# SkeinTwister.net
KiCad netlist of a schematic drawn in EAGLE
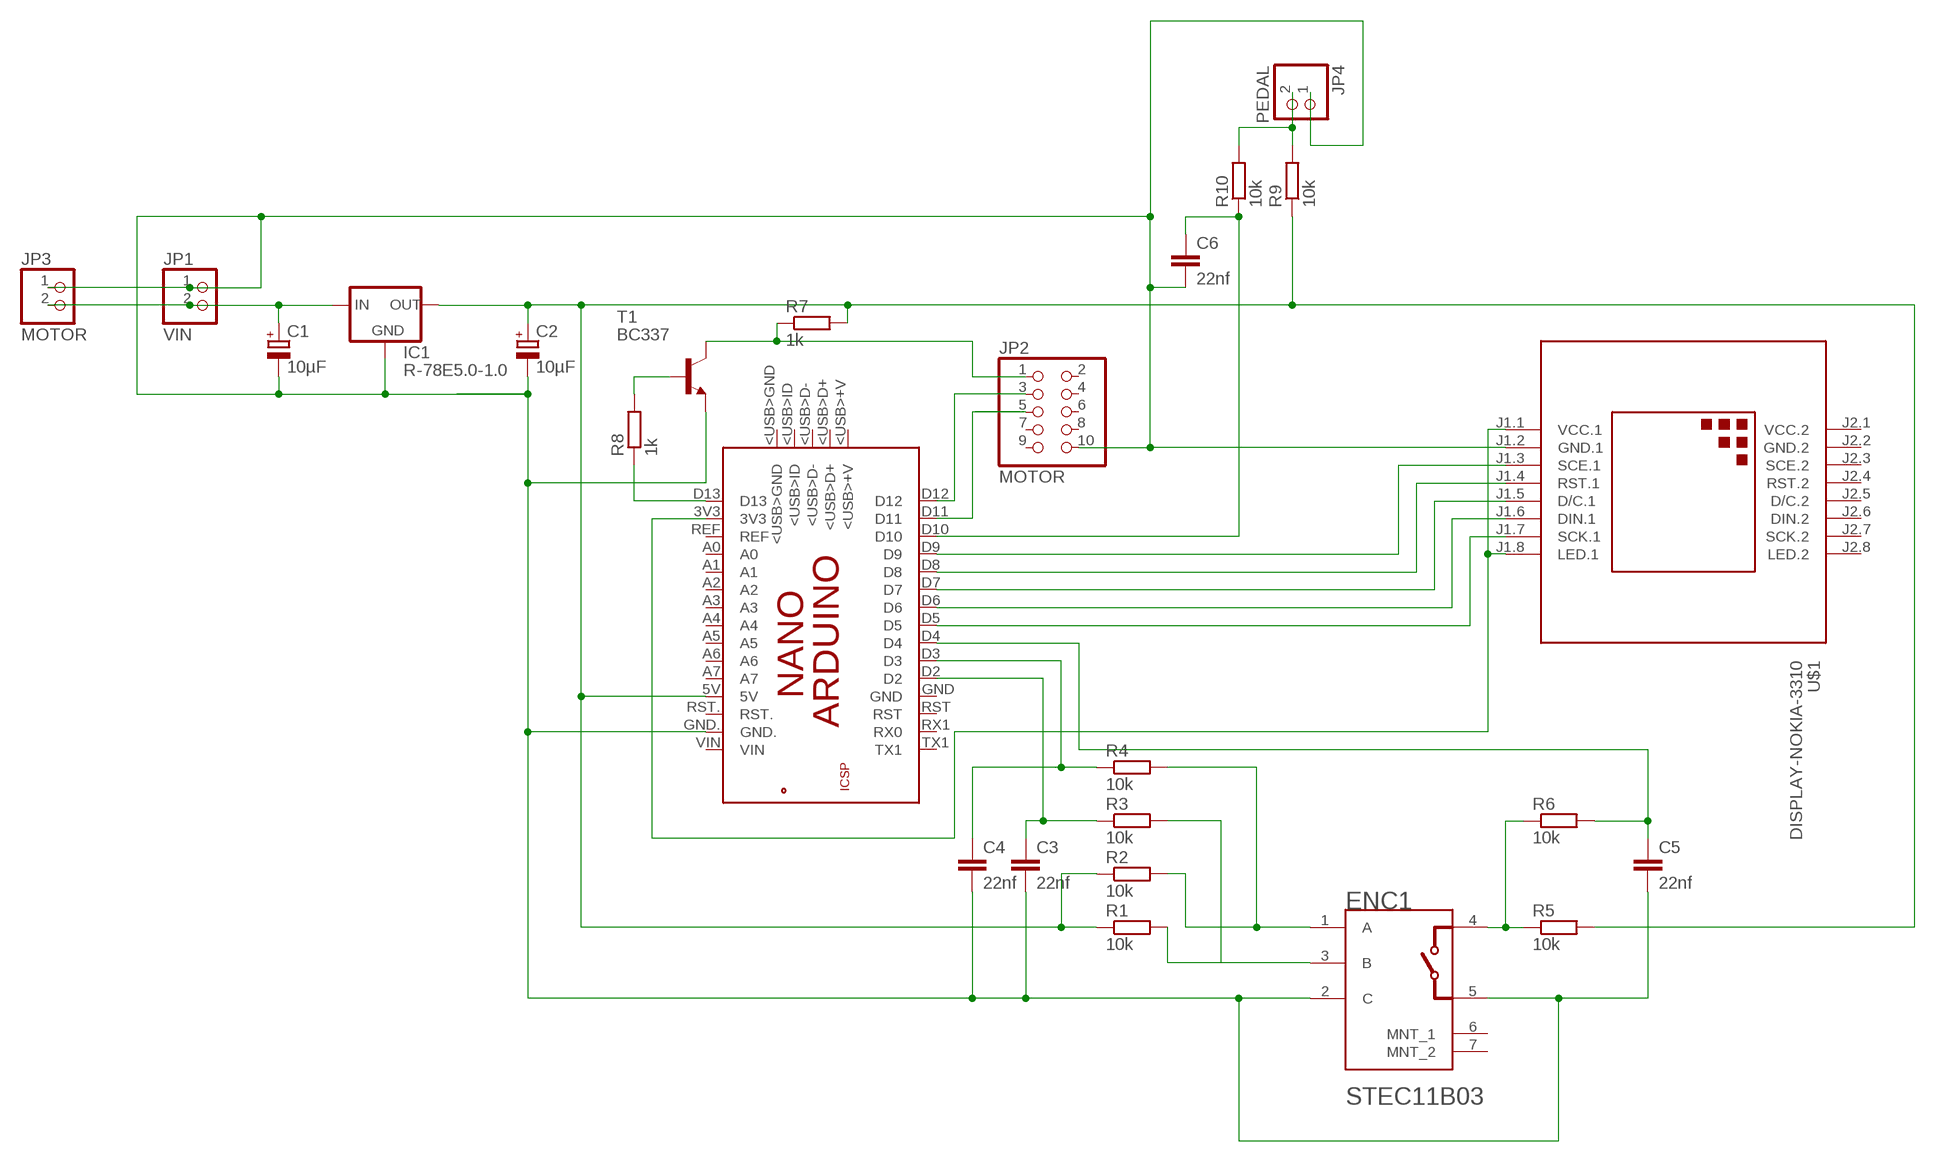
[diagram p0: schematic, sheet 1]

(export (version "E")
  (design (tool "Eeschema 10.0.6"))
  (components
    (comp (ref "C1")
      (value "10µF")
      (footprint "eagle-import:E5-5")
      (libsource (lib "eagle-import") (part "CPOL-EUE5-5"))
    )
    (comp (ref "C2")
      (value "10µF")
      (footprint "eagle-import:E5-5")
      (libsource (lib "eagle-import") (part "CPOL-EUE5-5"))
    )
    (comp (ref "C3")
      (value "22nf")
      (footprint "eagle-import:C025-024X044")
      (libsource (lib "eagle-import") (part "C-EU025-024X044"))
    )
    (comp (ref "C4")
      (value "22nf")
      (footprint "eagle-import:C025-024X044")
      (libsource (lib "eagle-import") (part "C-EU025-024X044"))
    )
    (comp (ref "C5")
      (value "22nf")
      (footprint "eagle-import:C025-024X044")
      (libsource (lib "eagle-import") (part "C-EU025-024X044"))
    )
    (comp (ref "C6")
      (value "22nf")
      (footprint "eagle-import:C025-024X044")
      (libsource (lib "eagle-import") (part "C-EU025-024X044"))
    )
    (comp (ref "ENC1")
      (value "ALPS_STEC11B03ALPS_STEC11B03_0_0")
      (footprint "eagle-import:ALPS_STEC11B03_0")
      (fields (field (name "MF") "ALPS") (field (name "MPN") "STEC11B03"))
      (libsource (lib "eagle-import") (part "ALPS_STEC11B03ALPS_STEC11B03_0_0"))
    )
    (comp (ref "IC1")
      (value "R-78E5.0-1.0")
      (footprint "eagle-import:SIP3")
      (fields (field (name "MF") "Recom") (field (name "MPN") "R-785.0-1.0"))
      (libsource (lib "eagle-import") (part "R-78E-1.05.0"))
    )
    (comp (ref "JP1")
      (value "VIN")
      (footprint "eagle-import:1X02")
      (libsource (lib "eagle-import") (part "PINHD-1X2"))
    )
    (comp (ref "JP2")
      (value "MOTOR")
      (footprint "eagle-import:2X05")
      (libsource (lib "eagle-import") (part "PINHD-2X5"))
    )
    (comp (ref "JP3")
      (value "MOTOR")
      (footprint "eagle-import:1X02")
      (libsource (lib "eagle-import") (part "PINHD-1X2"))
    )
    (comp (ref "JP4")
      (value "PEDAL")
      (footprint "eagle-import:1X02")
      (libsource (lib "eagle-import") (part "PINHD-1X2"))
    )
    (comp (ref "PCB2")
      (value "ARDUINO_NANO")
      (footprint "eagle-import:ARDUINO_NANO")
      (libsource (lib "eagle-import") (part "ARDUINO_NANO"))
    )
    (comp (ref "R1")
      (value "10k")
      (footprint "eagle-import:0204_5")
      (libsource (lib "eagle-import") (part "R-EU_0204/5"))
    )
    (comp (ref "R2")
      (value "10k")
      (footprint "eagle-import:0204_5")
      (libsource (lib "eagle-import") (part "R-EU_0204/5"))
    )
    (comp (ref "R3")
      (value "10k")
      (footprint "eagle-import:0204_5")
      (libsource (lib "eagle-import") (part "R-EU_0204/5"))
    )
    (comp (ref "R4")
      (value "10k")
      (footprint "eagle-import:0204_5")
      (libsource (lib "eagle-import") (part "R-EU_0204/5"))
    )
    (comp (ref "R5")
      (value "10k")
      (footprint "eagle-import:0204_5")
      (libsource (lib "eagle-import") (part "R-EU_0204/5"))
    )
    (comp (ref "R6")
      (value "10k")
      (footprint "eagle-import:0204_5")
      (libsource (lib "eagle-import") (part "R-EU_0204/5"))
    )
    (comp (ref "R7")
      (value "1k")
      (footprint "eagle-import:0204_5")
      (libsource (lib "eagle-import") (part "R-EU_0204/5"))
    )
    (comp (ref "R8")
      (value "1k")
      (footprint "eagle-import:0204_5")
      (libsource (lib "eagle-import") (part "R-EU_0204/5"))
    )
    (comp (ref "R9")
      (value "10k")
      (footprint "eagle-import:0204_5")
      (libsource (lib "eagle-import") (part "R-EU_0204/5"))
    )
    (comp (ref "R10")
      (value "10k")
      (footprint "eagle-import:0204_5")
      (libsource (lib "eagle-import") (part "R-EU_0204/5"))
    )
    (comp (ref "T1")
      (value "BC337")
      (footprint "eagle-import:TO92")
      (libsource (lib "eagle-import") (part "BC337"))
    )
    (comp (ref "U$1")
      (value "DISPLAY-NOKIA-3310")
      (footprint "eagle-import:DISPLAY-NOKIA-3310")
      (libsource (lib "eagle-import") (part "DISPLAY-NOKIA-3310"))
    )
  )
  (nets
    (net (code "1") (name "/GND.2") (class "Default")
      (node (ref "U$1") (pin "J2.2") (pinfunction "GND.2_J2.2") (pintype "power_in"))
    )
    (net (code "2") (name "/VCC.2") (class "Default")
      (node (ref "U$1") (pin "J2.1") (pinfunction "VCC.2_J2.1") (pintype "power_in"))
    )
    (net (code "3") (name "Net-(C3-Pad1)") (class "Default")
      (node (ref "C3") (pin "1") (pinfunction "1_1") (pintype "passive"))
      (node (ref "PCB2") (pin "D2") (pinfunction "D2_D2") (pintype "bidirectional"))
      (node (ref "R3") (pin "1") (pinfunction "1_1") (pintype "passive"))
    )
    (net (code "4") (name "Net-(C4-Pad1)") (class "Default")
      (node (ref "C4") (pin "1") (pinfunction "1_1") (pintype "passive"))
      (node (ref "PCB2") (pin "D3") (pinfunction "D3_D3") (pintype "bidirectional"))
      (node (ref "R4") (pin "1") (pinfunction "1_1") (pintype "passive"))
    )
    (net (code "5") (name "Net-(C5-Pad1)") (class "Default")
      (node (ref "C5") (pin "1") (pinfunction "1_1") (pintype "passive"))
      (node (ref "PCB2") (pin "D4") (pinfunction "D4_D4") (pintype "bidirectional"))
      (node (ref "R6") (pin "2") (pinfunction "2_2") (pintype "passive"))
    )
    (net (code "6") (name "Net-(C6-Pad1)") (class "Default")
      (node (ref "C6") (pin "1") (pinfunction "1_1") (pintype "passive"))
      (node (ref "PCB2") (pin "D10") (pinfunction "D10_D10") (pintype "bidirectional"))
      (node (ref "R10") (pin "1") (pinfunction "1_1") (pintype "passive"))
    )
    (net (code "7") (name "Net-(ENC1-A)") (class "Default")
      (node (ref "ENC1") (pin "1") (pinfunction "A_1") (pintype "passive"))
      (node (ref "R2") (pin "2") (pinfunction "2_2") (pintype "passive"))
      (node (ref "R4") (pin "2") (pinfunction "2_2") (pintype "passive"))
    )
    (net (code "8") (name "Net-(ENC1-B)") (class "Default")
      (node (ref "ENC1") (pin "3") (pinfunction "B_3") (pintype "passive"))
      (node (ref "R1") (pin "2") (pinfunction "2_2") (pintype "passive"))
      (node (ref "R3") (pin "2") (pinfunction "2_2") (pintype "passive"))
    )
    (net (code "9") (name "Net-(ENC1-C)") (class "Default")
      (node (ref "C1") (pin "-") (pinfunction "-_-") (pintype "passive"))
      (node (ref "C2") (pin "-") (pinfunction "-_-") (pintype "passive"))
      (node (ref "C3") (pin "2") (pinfunction "2_2") (pintype "passive"))
      (node (ref "C4") (pin "2") (pinfunction "2_2") (pintype "passive"))
      (node (ref "C5") (pin "2") (pinfunction "2_2") (pintype "passive"))
      (node (ref "C6") (pin "2") (pinfunction "2_2") (pintype "passive"))
      (node (ref "ENC1") (pin "2") (pinfunction "C_2") (pintype "passive"))
      (node (ref "ENC1") (pin "5") (pinfunction "5_5") (pintype "passive"))
      (node (ref "IC1") (pin "2") (pinfunction "GND_2") (pintype "input"))
      (node (ref "JP1") (pin "1") (pinfunction "1_1") (pintype "passive"))
      (node (ref "JP2") (pin "10") (pinfunction "10_10") (pintype "passive"))
      (node (ref "JP3") (pin "1") (pinfunction "1_1") (pintype "passive"))
      (node (ref "JP4") (pin "1") (pinfunction "1_1") (pintype "passive"))
      (node (ref "PCB2") (pin "GND.") (pinfunction "GND._GND.") (pintype "bidirectional"))
      (node (ref "T1") (pin "1") (pinfunction "E_1") (pintype "passive"))
      (node (ref "U$1") (pin "J1.2") (pinfunction "GND.1_J1.2") (pintype "power_in"))
    )
    (net (code "10") (name "Net-(ENC1-Pad4)") (class "Default")
      (node (ref "ENC1") (pin "4") (pinfunction "4_4") (pintype "passive"))
      (node (ref "R5") (pin "1") (pinfunction "1_1") (pintype "passive"))
      (node (ref "R6") (pin "1") (pinfunction "1_1") (pintype "passive"))
    )
    (net (code "11") (name "Net-(IC1-IN)") (class "Default")
      (node (ref "C1") (pin "+") (pinfunction "+_+") (pintype "passive"))
      (node (ref "IC1") (pin "1") (pinfunction "IN_1") (pintype "input"))
      (node (ref "JP1") (pin "2") (pinfunction "2_2") (pintype "passive"))
      (node (ref "JP3") (pin "2") (pinfunction "2_2") (pintype "passive"))
    )
    (net (code "12") (name "Net-(IC1-OUT)") (class "Default")
      (node (ref "C2") (pin "+") (pinfunction "+_+") (pintype "passive"))
      (node (ref "IC1") (pin "3") (pinfunction "OUT_3") (pintype "passive"))
      (node (ref "PCB2") (pin "5V") (pinfunction "5V_5V") (pintype "bidirectional"))
      (node (ref "R1") (pin "1") (pinfunction "1_1") (pintype "passive"))
      (node (ref "R2") (pin "1") (pinfunction "1_1") (pintype "passive"))
      (node (ref "R5") (pin "2") (pinfunction "2_2") (pintype "passive"))
      (node (ref "R7") (pin "2") (pinfunction "2_2") (pintype "passive"))
      (node (ref "R9") (pin "1") (pinfunction "1_1") (pintype "passive"))
    )
    (net (code "13") (name "Net-(JP2-Pad3)") (class "Default")
      (node (ref "JP2") (pin "3") (pinfunction "3_3") (pintype "passive"))
      (node (ref "PCB2") (pin "D12") (pinfunction "D12_D12") (pintype "bidirectional"))
    )
    (net (code "14") (name "Net-(JP2-Pad5)") (class "Default")
      (node (ref "JP2") (pin "5") (pinfunction "5_5") (pintype "passive"))
      (node (ref "PCB2") (pin "D11") (pinfunction "D11_D11") (pintype "bidirectional"))
    )
    (net (code "15") (name "Net-(JP4-Pad2)") (class "Default")
      (node (ref "JP4") (pin "2") (pinfunction "2_2") (pintype "passive"))
      (node (ref "R10") (pin "2") (pinfunction "2_2") (pintype "passive"))
      (node (ref "R9") (pin "2") (pinfunction "2_2") (pintype "passive"))
    )
    (net (code "16") (name "Net-(PCB2-PadD13)") (class "Default")
      (node (ref "PCB2") (pin "D13") (pinfunction "D13_D13") (pintype "bidirectional"))
      (node (ref "R8") (pin "1") (pinfunction "1_1") (pintype "passive"))
    )
    (net (code "17") (name "Net-(T1-B)") (class "Default")
      (node (ref "R8") (pin "2") (pinfunction "2_2") (pintype "passive"))
      (node (ref "T1") (pin "2") (pinfunction "B_2") (pintype "passive"))
    )
    (net (code "18") (name "Net-(T1-C)") (class "Default")
      (node (ref "JP2") (pin "1") (pinfunction "1_1") (pintype "passive"))
      (node (ref "R7") (pin "1") (pinfunction "1_1") (pintype "passive"))
      (node (ref "T1") (pin "3") (pinfunction "C_3") (pintype "passive"))
    )
    (net (code "19") (name "Net-(U$1-DIN.1)") (class "Default")
      (node (ref "PCB2") (pin "D6") (pinfunction "D6_D6") (pintype "bidirectional"))
      (node (ref "U$1") (pin "J1.6") (pinfunction "DIN.1_J1.6") (pintype "bidirectional"))
    )
    (net (code "20") (name "Net-(U$1-D{slash}C.1)") (class "Default")
      (node (ref "PCB2") (pin "D7") (pinfunction "D7_D7") (pintype "bidirectional"))
      (node (ref "U$1") (pin "J1.5") (pinfunction "D/C.1_J1.5") (pintype "bidirectional"))
    )
    (net (code "21") (name "Net-(U$1-LED.1)") (class "Default")
      (node (ref "PCB2") (pin "3V3") (pinfunction "3V3_3V3") (pintype "bidirectional"))
      (node (ref "U$1") (pin "J1.1") (pinfunction "VCC.1_J1.1") (pintype "power_in"))
      (node (ref "U$1") (pin "J1.8") (pinfunction "LED.1_J1.8") (pintype "input"))
    )
    (net (code "22") (name "Net-(U$1-RST.1)") (class "Default")
      (node (ref "PCB2") (pin "D8") (pinfunction "D8_D8") (pintype "bidirectional"))
      (node (ref "U$1") (pin "J1.4") (pinfunction "RST.1_J1.4") (pintype "bidirectional"))
    )
    (net (code "23") (name "Net-(U$1-SCE.1)") (class "Default")
      (node (ref "PCB2") (pin "D9") (pinfunction "D9_D9") (pintype "bidirectional"))
      (node (ref "U$1") (pin "J1.3") (pinfunction "SCE.1_J1.3") (pintype "bidirectional"))
    )
    (net (code "24") (name "Net-(U$1-SCK.1)") (class "Default")
      (node (ref "PCB2") (pin "D5") (pinfunction "D5_D5") (pintype "bidirectional"))
      (node (ref "U$1") (pin "J1.7") (pinfunction "SCK.1_J1.7") (pintype "bidirectional"))
    )
    (net (code "25") (name "unconnected-(ENC1-MNT_1-Pad6)") (class "Default")
      (node (ref "ENC1") (pin "6") (pinfunction "MNT_1_6") (pintype "passive"))
    )
    (net (code "26") (name "unconnected-(ENC1-MNT_2-Pad7)") (class "Default")
      (node (ref "ENC1") (pin "7") (pinfunction "MNT_2_7") (pintype "passive"))
    )
    (net (code "27") (name "unconnected-(JP2-Pad2)") (class "Default")
      (node (ref "JP2") (pin "2") (pinfunction "2_2") (pintype "passive"))
    )
    (net (code "28") (name "unconnected-(JP2-Pad4)") (class "Default")
      (node (ref "JP2") (pin "4") (pinfunction "4_4") (pintype "passive"))
    )
    (net (code "29") (name "unconnected-(JP2-Pad6)") (class "Default")
      (node (ref "JP2") (pin "6") (pinfunction "6_6") (pintype "passive"))
    )
    (net (code "30") (name "unconnected-(JP2-Pad7)") (class "Default")
      (node (ref "JP2") (pin "7") (pinfunction "7_7") (pintype "passive"))
    )
    (net (code "31") (name "unconnected-(JP2-Pad8)") (class "Default")
      (node (ref "JP2") (pin "8") (pinfunction "8_8") (pintype "passive"))
    )
    (net (code "32") (name "unconnected-(JP2-Pad9)") (class "Default")
      (node (ref "JP2") (pin "9") (pinfunction "9_9") (pintype "passive"))
    )
    (net (code "33") (name "unconnected-(PCB2-Pad5V.)") (class "Default")
      (node (ref "PCB2") (pin "5V.") (pinfunction "5V._5V.") (pintype "bidirectional"))
    )
    (net (code "34") (name "unconnected-(PCB2-Pad<USB>+V)") (class "Default")
      (node (ref "PCB2") (pin "<USB>+V") (pinfunction "<USB>+V_<USB>+V") (pintype "bidirectional"))
    )
    (net (code "35") (name "unconnected-(PCB2-Pad<USB>D+)") (class "Default")
      (node (ref "PCB2") (pin "<USB>D+") (pinfunction "<USB>D+_<USB>D+") (pintype "bidirectional"))
    )
    (net (code "36") (name "unconnected-(PCB2-Pad<USB>D-)") (class "Default")
      (node (ref "PCB2") (pin "<USB>D-") (pinfunction "<USB>D-_<USB>D-") (pintype "bidirectional"))
    )
    (net (code "37") (name "unconnected-(PCB2-Pad<USB>GND)") (class "Default")
      (node (ref "PCB2") (pin "<USB>GND") (pinfunction "<USB>GND_<USB>GND") (pintype "bidirectional"))
    )
    (net (code "38") (name "unconnected-(PCB2-Pad<USB>ID)") (class "Default")
      (node (ref "PCB2") (pin "<USB>ID") (pinfunction "<USB>ID_<USB>ID") (pintype "bidirectional"))
    )
    (net (code "39") (name "unconnected-(PCB2-PadA0)") (class "Default")
      (node (ref "PCB2") (pin "A0") (pinfunction "A0_A0") (pintype "bidirectional"))
    )
    (net (code "40") (name "unconnected-(PCB2-PadA1)") (class "Default")
      (node (ref "PCB2") (pin "A1") (pinfunction "A1_A1") (pintype "bidirectional"))
    )
    (net (code "41") (name "unconnected-(PCB2-PadA2)") (class "Default")
      (node (ref "PCB2") (pin "A2") (pinfunction "A2_A2") (pintype "bidirectional"))
    )
    (net (code "42") (name "unconnected-(PCB2-PadA3)") (class "Default")
      (node (ref "PCB2") (pin "A3") (pinfunction "A3_A3") (pintype "bidirectional"))
    )
    (net (code "43") (name "unconnected-(PCB2-PadA4)") (class "Default")
      (node (ref "PCB2") (pin "A4") (pinfunction "A4_A4") (pintype "bidirectional"))
    )
    (net (code "44") (name "unconnected-(PCB2-PadA5)") (class "Default")
      (node (ref "PCB2") (pin "A5") (pinfunction "A5_A5") (pintype "bidirectional"))
    )
    (net (code "45") (name "unconnected-(PCB2-PadA6)") (class "Default")
      (node (ref "PCB2") (pin "A6") (pinfunction "A6_A6") (pintype "bidirectional"))
    )
    (net (code "46") (name "unconnected-(PCB2-PadA7)") (class "Default")
      (node (ref "PCB2") (pin "A7") (pinfunction "A7_A7") (pintype "bidirectional"))
    )
    (net (code "47") (name "unconnected-(PCB2-PadGND)") (class "Default")
      (node (ref "PCB2") (pin "GND") (pinfunction "GND_GND") (pintype "bidirectional"))
    )
    (net (code "48") (name "unconnected-(PCB2-PadGND_)") (class "Default")
      (node (ref "PCB2") (pin "GND_") (pinfunction "GND__GND_") (pintype "bidirectional"))
    )
    (net (code "49") (name "unconnected-(PCB2-PadMISO)") (class "Default")
      (node (ref "PCB2") (pin "MISO") (pinfunction "MISO_MISO") (pintype "bidirectional"))
    )
    (net (code "50") (name "unconnected-(PCB2-PadMOSI)") (class "Default")
      (node (ref "PCB2") (pin "MOSI") (pinfunction "MOSI_MOSI") (pintype "bidirectional"))
    )
    (net (code "51") (name "unconnected-(PCB2-PadREF)") (class "Default")
      (node (ref "PCB2") (pin "REF") (pinfunction "REF_REF") (pintype "bidirectional"))
    )
    (net (code "52") (name "unconnected-(PCB2-PadRESET..)") (class "Default")
      (node (ref "PCB2") (pin "RESET..") (pinfunction "RESET.._RESET..") (pintype "bidirectional"))
    )
    (net (code "53") (name "unconnected-(PCB2-PadRST)") (class "Default")
      (node (ref "PCB2") (pin "RST") (pinfunction "RST_RST") (pintype "bidirectional"))
    )
    (net (code "54") (name "unconnected-(PCB2-PadRST.)") (class "Default")
      (node (ref "PCB2") (pin "RST.") (pinfunction "RST._RST.") (pintype "bidirectional"))
    )
    (net (code "55") (name "unconnected-(PCB2-PadSCK)") (class "Default")
      (node (ref "PCB2") (pin "SCK") (pinfunction "SCK_SCK") (pintype "bidirectional"))
    )
    (net (code "56") (name "unconnected-(PCB2-PadTX1)") (class "Default")
      (node (ref "PCB2") (pin "TX1") (pinfunction "TX1_TX1") (pintype "bidirectional"))
    )
    (net (code "57") (name "unconnected-(PCB2-PadVIN)") (class "Default")
      (node (ref "PCB2") (pin "VIN") (pinfunction "VIN_VIN") (pintype "bidirectional"))
    )
    (net (code "58") (name "unconnected-(PCB2-RX0-PadRX1)") (class "Default")
      (node (ref "PCB2") (pin "RX1") (pinfunction "RX0_RX1") (pintype "bidirectional"))
    )
    (net (code "59") (name "unconnected-(U$1-DIN.2-PadJ2.6)") (class "Default")
      (node (ref "U$1") (pin "J2.6") (pinfunction "DIN.2_J2.6") (pintype "bidirectional"))
    )
    (net (code "60") (name "unconnected-(U$1-D{slash}C.2-PadJ2.5)") (class "Default")
      (node (ref "U$1") (pin "J2.5") (pinfunction "D/C.2_J2.5") (pintype "bidirectional"))
    )
    (net (code "61") (name "unconnected-(U$1-LED.2-PadJ2.8)") (class "Default")
      (node (ref "U$1") (pin "J2.8") (pinfunction "LED.2_J2.8") (pintype "input"))
    )
    (net (code "62") (name "unconnected-(U$1-RST.2-PadJ2.4)") (class "Default")
      (node (ref "U$1") (pin "J2.4") (pinfunction "RST.2_J2.4") (pintype "bidirectional"))
    )
    (net (code "63") (name "unconnected-(U$1-SCE.2-PadJ2.3)") (class "Default")
      (node (ref "U$1") (pin "J2.3") (pinfunction "SCE.2_J2.3") (pintype "bidirectional"))
    )
    (net (code "64") (name "unconnected-(U$1-SCK.2-PadJ2.7)") (class "Default")
      (node (ref "U$1") (pin "J2.7") (pinfunction "SCK.2_J2.7") (pintype "bidirectional"))
    )
  )
)
